# automation-v2.net
KiCad netlist of a schematic drawn in EAGLE
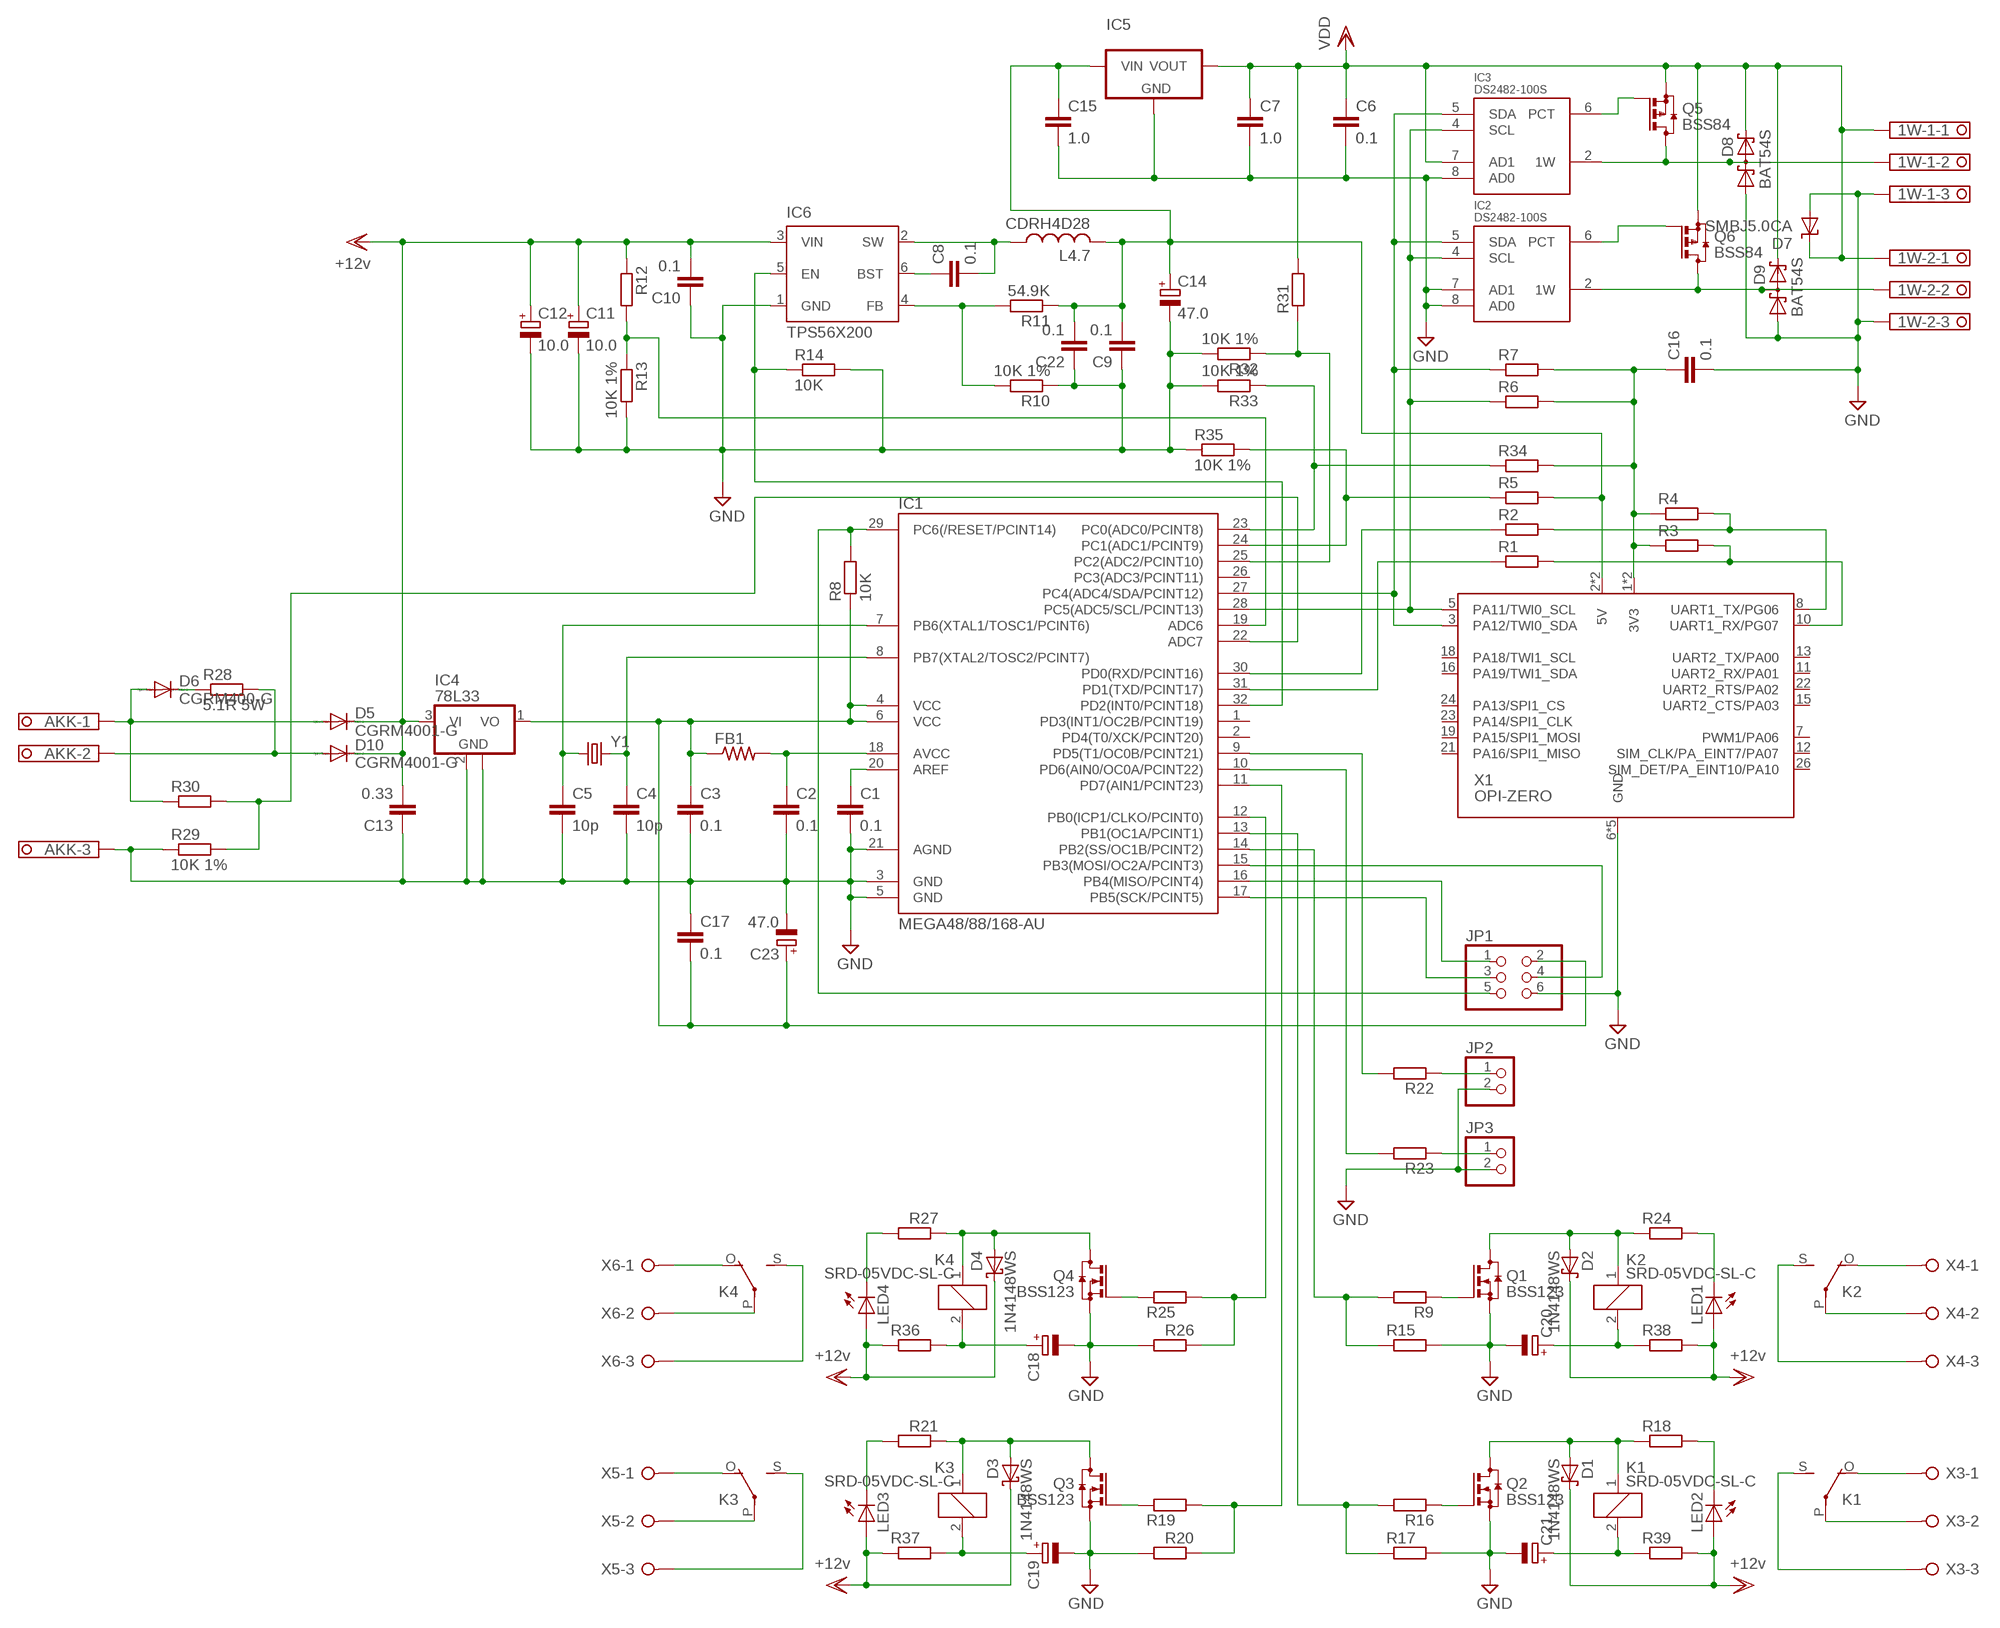
[diagram p0: schematic, sheet 1]

(export (version "E")
  (design (tool "Eeschema 10.0.6"))
  (components
    (comp (ref "1W-1")
      (value "1751251")
      (footprint "eagle-import:1751251")
      (libsource (lib "eagle-import") (part "1751251"))
    )
    (comp (ref "1W-2")
      (value "1751251")
      (footprint "eagle-import:1751251")
      (libsource (lib "eagle-import") (part "1751251"))
    )
    (comp (ref "AKK")
      (value "1751251")
      (footprint "eagle-import:1751251")
      (libsource (lib "eagle-import") (part "1751251"))
    )
    (comp (ref "C1")
      (value "0.1")
      (footprint "eagle-import:C0603")
      (libsource (lib "eagle-import") (part "C-EUC0603"))
    )
    (comp (ref "C2")
      (value "0.1")
      (footprint "eagle-import:C0603")
      (libsource (lib "eagle-import") (part "C-EUC0603"))
    )
    (comp (ref "C3")
      (value "0.1")
      (footprint "eagle-import:C0603")
      (libsource (lib "eagle-import") (part "C-EUC0603"))
    )
    (comp (ref "C4")
      (value "10p")
      (footprint "eagle-import:C0603")
      (libsource (lib "eagle-import") (part "C-EUC0603"))
    )
    (comp (ref "C5")
      (value "10p")
      (footprint "eagle-import:C0603")
      (libsource (lib "eagle-import") (part "C-EUC0603"))
    )
    (comp (ref "C6")
      (value "0.1")
      (footprint "eagle-import:C0603")
      (libsource (lib "eagle-import") (part "C-EUC0603"))
    )
    (comp (ref "C7")
      (value "1.0")
      (footprint "eagle-import:C0805")
      (libsource (lib "eagle-import") (part "C-EUC0805"))
    )
    (comp (ref "C8")
      (value "0.1")
      (footprint "eagle-import:C0805")
      (libsource (lib "eagle-import") (part "C-EUC0805"))
    )
    (comp (ref "C9")
      (value "0.1")
      (footprint "eagle-import:C0805")
      (libsource (lib "eagle-import") (part "C-EUC0805"))
    )
    (comp (ref "C10")
      (value "0.1")
      (footprint "eagle-import:C0805")
      (libsource (lib "eagle-import") (part "C-EUC0805"))
    )
    (comp (ref "C11")
      (value "10.0")
      (footprint "eagle-import:C_6032-28R")
      (libsource (lib "eagle-import") (part "CPOL-EUC/6032-28R"))
    )
    (comp (ref "C12")
      (value "10.0")
      (footprint "eagle-import:C_6032-28R")
      (libsource (lib "eagle-import") (part "CPOL-EUC/6032-28R"))
    )
    (comp (ref "C13")
      (value "0.33")
      (footprint "eagle-import:C0805")
      (libsource (lib "eagle-import") (part "C-EUC0805"))
    )
    (comp (ref "C14")
      (value "47.0")
      (footprint "eagle-import:B_3528-21R")
      (libsource (lib "eagle-import") (part "CPOL-EUB/3528-21R"))
    )
    (comp (ref "C15")
      (value "1.0")
      (footprint "eagle-import:C0805")
      (libsource (lib "eagle-import") (part "C-EUC0805"))
    )
    (comp (ref "C16")
      (value "0.1")
      (footprint "eagle-import:C0603")
      (libsource (lib "eagle-import") (part "C-EUC0603"))
    )
    (comp (ref "C17")
      (value "0.1")
      (footprint "eagle-import:C0603")
      (libsource (lib "eagle-import") (part "C-EUC0603"))
    )
    (comp (ref "C18")
      (value "CPOL-EUE5-10.5")
      (footprint "eagle-import:E5-10,5")
      (libsource (lib "eagle-import") (part "CPOL-EUE5-10.5"))
    )
    (comp (ref "C19")
      (value "CPOL-EUE5-10.5")
      (footprint "eagle-import:E5-10,5")
      (libsource (lib "eagle-import") (part "CPOL-EUE5-10.5"))
    )
    (comp (ref "C20")
      (value "CPOL-EUE5-10.5")
      (footprint "eagle-import:E5-10,5")
      (libsource (lib "eagle-import") (part "CPOL-EUE5-10.5"))
    )
    (comp (ref "C21")
      (value "CPOL-EUE5-10.5")
      (footprint "eagle-import:E5-10,5")
      (libsource (lib "eagle-import") (part "CPOL-EUE5-10.5"))
    )
    (comp (ref "C22")
      (value "0.1")
      (footprint "eagle-import:C0805")
      (libsource (lib "eagle-import") (part "C-EUC0805"))
    )
    (comp (ref "C23")
      (value "47.0")
      (footprint "eagle-import:B_3528-21R")
      (libsource (lib "eagle-import") (part "CPOL-EUB/3528-21R"))
    )
    (comp (ref "D1")
      (value "1N4148WS")
      (footprint "eagle-import:SOD323_ST")
      (libsource (lib "eagle-import") (part "BAT60J"))
    )
    (comp (ref "D2")
      (value "1N4148WS")
      (footprint "eagle-import:SOD323_ST")
      (libsource (lib "eagle-import") (part "BAT60J"))
    )
    (comp (ref "D3")
      (value "1N4148WS")
      (footprint "eagle-import:SOD323_ST")
      (libsource (lib "eagle-import") (part "BAT60J"))
    )
    (comp (ref "D4")
      (value "1N4148WS")
      (footprint "eagle-import:SOD323_ST")
      (libsource (lib "eagle-import") (part "BAT60J"))
    )
    (comp (ref "D5")
      (value "CGRM4001-G")
      (footprint "eagle-import:SOD-123_MINI-SMA")
      (libsource (lib "eagle-import") (part "CGRM400-G1"))
    )
    (comp (ref "D6")
      (value "CGRM400-G")
      (footprint "eagle-import:SOD-123_MINI-SMA")
      (libsource (lib "eagle-import") (part "CGRM400-G1"))
    )
    (comp (ref "D7")
      (value "SMBJ5.0CA")
      (footprint "eagle-import:SMBJ")
      (libsource (lib "eagle-import") (part "SUPPRESSOR-SMBJ"))
    )
    (comp (ref "D8")
      (value "BAT54S")
      (footprint "eagle-import:SOT23")
      (libsource (lib "eagle-import") (part "BAT54S"))
    )
    (comp (ref "D9")
      (value "BAT54S")
      (footprint "eagle-import:SOT23")
      (libsource (lib "eagle-import") (part "BAT54S"))
    )
    (comp (ref "D10")
      (value "CGRM4001-G")
      (footprint "eagle-import:SOD-123_MINI-SMA")
      (libsource (lib "eagle-import") (part "CGRM400-G1"))
    )
    (comp (ref "FB1")
      (value "R-US_R0805")
      (footprint "eagle-import:R0805")
      (libsource (lib "eagle-import") (part "R-US_R0805"))
    )
    (comp (ref "IC1")
      (value "MEGA48/88/168-AU")
      (footprint "eagle-import:TQFP32-08")
      (libsource (lib "eagle-import") (part "MEGA48/88/168-AU"))
    )
    (comp (ref "IC2")
      (value "DS2482-100S")
      (footprint "eagle-import:SO08")
      (libsource (lib "eagle-import") (part "DS2482-100S"))
    )
    (comp (ref "IC3")
      (value "DS2482-100S")
      (footprint "eagle-import:SO08")
      (libsource (lib "eagle-import") (part "DS2482-100S"))
    )
    (comp (ref "IC4")
      (value "78L33")
      (footprint "eagle-import:SOT89")
      (libsource (lib "eagle-import") (part "78LF05"))
    )
    (comp (ref "IC5")
      (value "MCP1702SOT23")
      (footprint "eagle-import:SOT23-3-ROTATED")
      (libsource (lib "eagle-import") (part "MCP1702SOT23"))
    )
    (comp (ref "IC6")
      (value "TPS56X200")
      (footprint "eagle-import:TSOT23-6_DDC")
      (libsource (lib "eagle-import") (part "TPS56X200"))
    )
    (comp (ref "JP1")
      (value "PINHD-2X3")
      (footprint "eagle-import:2X03")
      (libsource (lib "eagle-import") (part "PINHD-2X3"))
    )
    (comp (ref "JP2")
      (value "PINHD-1X2")
      (footprint "eagle-import:1X02")
      (libsource (lib "eagle-import") (part "PINHD-1X2"))
    )
    (comp (ref "JP3")
      (value "PINHD-1X2")
      (footprint "eagle-import:1X02")
      (libsource (lib "eagle-import") (part "PINHD-1X2"))
    )
    (comp (ref "K1")
      (value "SRD-05VDC-SL-C")
      (footprint "eagle-import:NRP18")
      (libsource (lib "eagle-import") (part "ZF112S"))
    )
    (comp (ref "K2")
      (value "SRD-05VDC-SL-C")
      (footprint "eagle-import:NRP18")
      (libsource (lib "eagle-import") (part "ZF112S"))
    )
    (comp (ref "K3")
      (value "SRD-05VDC-SL-C")
      (footprint "eagle-import:NRP18")
      (libsource (lib "eagle-import") (part "ZF112S"))
    )
    (comp (ref "K4")
      (value "SRD-05VDC-SL-C")
      (footprint "eagle-import:NRP18")
      (libsource (lib "eagle-import") (part "ZF112S"))
    )
    (comp (ref "L4.7")
      (value "CDRH4D28")
      (footprint "eagle-import:CDRH4D28")
      (libsource (lib "eagle-import") (part "CDRH4D28"))
    )
    (comp (ref "LED1")
      (value "LEDSML0805")
      (footprint "eagle-import:SML0805")
      (libsource (lib "eagle-import") (part "LEDSML0805"))
    )
    (comp (ref "LED2")
      (value "LEDSML0805")
      (footprint "eagle-import:SML0805")
      (libsource (lib "eagle-import") (part "LEDSML0805"))
    )
    (comp (ref "LED3")
      (value "LEDSML0805")
      (footprint "eagle-import:SML0805")
      (libsource (lib "eagle-import") (part "LEDSML0805"))
    )
    (comp (ref "LED4")
      (value "LEDSML0805")
      (footprint "eagle-import:SML0805")
      (libsource (lib "eagle-import") (part "LEDSML0805"))
    )
    (comp (ref "Q1")
      (value "BSS123")
      (footprint "eagle-import:SOT23")
      (libsource (lib "eagle-import") (part "BSS123"))
    )
    (comp (ref "Q2")
      (value "BSS123")
      (footprint "eagle-import:SOT23")
      (libsource (lib "eagle-import") (part "BSS123"))
    )
    (comp (ref "Q3")
      (value "BSS123")
      (footprint "eagle-import:SOT23")
      (libsource (lib "eagle-import") (part "BSS123"))
    )
    (comp (ref "Q4")
      (value "BSS123")
      (footprint "eagle-import:SOT23")
      (libsource (lib "eagle-import") (part "BSS123"))
    )
    (comp (ref "Q5")
      (value "BSS84")
      (footprint "eagle-import:SOT23")
      (libsource (lib "eagle-import") (part "BSS84"))
    )
    (comp (ref "Q6")
      (value "BSS84")
      (footprint "eagle-import:SOT23")
      (libsource (lib "eagle-import") (part "BSS84"))
    )
    (comp (ref "R1")
      (value "R-EU_R0603")
      (footprint "eagle-import:R0603")
      (libsource (lib "eagle-import") (part "R-EU_R0603"))
    )
    (comp (ref "R2")
      (value "R-EU_R0603")
      (footprint "eagle-import:R0603")
      (libsource (lib "eagle-import") (part "R-EU_R0603"))
    )
    (comp (ref "R3")
      (value "R-EU_R0603")
      (footprint "eagle-import:R0603")
      (libsource (lib "eagle-import") (part "R-EU_R0603"))
    )
    (comp (ref "R4")
      (value "R-EU_R0603")
      (footprint "eagle-import:R0603")
      (libsource (lib "eagle-import") (part "R-EU_R0603"))
    )
    (comp (ref "R5")
      (value "R-EU_R0603")
      (footprint "eagle-import:R0603")
      (libsource (lib "eagle-import") (part "R-EU_R0603"))
    )
    (comp (ref "R6")
      (value "R-EU_R0603")
      (footprint "eagle-import:R0603")
      (libsource (lib "eagle-import") (part "R-EU_R0603"))
    )
    (comp (ref "R7")
      (value "R-EU_R0603")
      (footprint "eagle-import:R0603")
      (libsource (lib "eagle-import") (part "R-EU_R0603"))
    )
    (comp (ref "R8")
      (value "10K")
      (footprint "eagle-import:R0603")
      (libsource (lib "eagle-import") (part "R-EU_R0603"))
    )
    (comp (ref "R9")
      (value "R-EU_R0603")
      (footprint "eagle-import:R0603")
      (libsource (lib "eagle-import") (part "R-EU_R0603"))
    )
    (comp (ref "R10")
      (value "10K 1%")
      (footprint "eagle-import:R0603")
      (libsource (lib "eagle-import") (part "R-EU_R0603"))
    )
    (comp (ref "R11")
      (value "54.9K")
      (footprint "eagle-import:R0603")
      (libsource (lib "eagle-import") (part "R-EU_R0603"))
    )
    (comp (ref "R12")
      (value "R-EU_R0603")
      (footprint "eagle-import:R0603")
      (libsource (lib "eagle-import") (part "R-EU_R0603"))
    )
    (comp (ref "R13")
      (value "10K 1%")
      (footprint "eagle-import:R0603")
      (libsource (lib "eagle-import") (part "R-EU_R0603"))
    )
    (comp (ref "R14")
      (value "10K")
      (footprint "eagle-import:R0603")
      (libsource (lib "eagle-import") (part "R-EU_R0603"))
    )
    (comp (ref "R15")
      (value "R-EU_R0603")
      (footprint "eagle-import:R0603")
      (libsource (lib "eagle-import") (part "R-EU_R0603"))
    )
    (comp (ref "R16")
      (value "R-EU_R0603")
      (footprint "eagle-import:R0603")
      (libsource (lib "eagle-import") (part "R-EU_R0603"))
    )
    (comp (ref "R17")
      (value "R-EU_R0603")
      (footprint "eagle-import:R0603")
      (libsource (lib "eagle-import") (part "R-EU_R0603"))
    )
    (comp (ref "R18")
      (value "R-EU_R0603")
      (footprint "eagle-import:R0603")
      (libsource (lib "eagle-import") (part "R-EU_R0603"))
    )
    (comp (ref "R19")
      (value "R-EU_R0603")
      (footprint "eagle-import:R0603")
      (libsource (lib "eagle-import") (part "R-EU_R0603"))
    )
    (comp (ref "R20")
      (value "R-EU_R0603")
      (footprint "eagle-import:R0603")
      (libsource (lib "eagle-import") (part "R-EU_R0603"))
    )
    (comp (ref "R21")
      (value "R-EU_R0603")
      (footprint "eagle-import:R0603")
      (libsource (lib "eagle-import") (part "R-EU_R0603"))
    )
    (comp (ref "R22")
      (value "R-EU_R0603")
      (footprint "eagle-import:R0603")
      (libsource (lib "eagle-import") (part "R-EU_R0603"))
    )
    (comp (ref "R23")
      (value "R-EU_R0603")
      (footprint "eagle-import:R0603")
      (libsource (lib "eagle-import") (part "R-EU_R0603"))
    )
    (comp (ref "R24")
      (value "R-EU_R0603")
      (footprint "eagle-import:R0603")
      (libsource (lib "eagle-import") (part "R-EU_R0603"))
    )
    (comp (ref "R25")
      (value "R-EU_R0603")
      (footprint "eagle-import:R0603")
      (libsource (lib "eagle-import") (part "R-EU_R0603"))
    )
    (comp (ref "R26")
      (value "R-EU_R0603")
      (footprint "eagle-import:R0603")
      (libsource (lib "eagle-import") (part "R-EU_R0603"))
    )
    (comp (ref "R27")
      (value "R-EU_R0603")
      (footprint "eagle-import:R0603")
      (libsource (lib "eagle-import") (part "R-EU_R0603"))
    )
    (comp (ref "R28")
      (value "5.1R 5W")
      (footprint "eagle-import:VTA55")
      (libsource (lib "eagle-import") (part "R-EU_VTA55"))
    )
    (comp (ref "R29")
      (value "10K 1%")
      (footprint "eagle-import:R0603")
      (libsource (lib "eagle-import") (part "R-EU_R0603"))
    )
    (comp (ref "R30")
      (value "R-EU_R0603")
      (footprint "eagle-import:R0603")
      (libsource (lib "eagle-import") (part "R-EU_R0603"))
    )
    (comp (ref "R31")
      (value "R-EU_R0603")
      (footprint "eagle-import:R0603")
      (libsource (lib "eagle-import") (part "R-EU_R0603"))
    )
    (comp (ref "R32")
      (value "10K 1%")
      (footprint "eagle-import:R0603")
      (libsource (lib "eagle-import") (part "R-EU_R0603"))
    )
    (comp (ref "R33")
      (value "10K 1%")
      (footprint "eagle-import:R0603")
      (libsource (lib "eagle-import") (part "R-EU_R0603"))
    )
    (comp (ref "R34")
      (value "R-EU_R0603")
      (footprint "eagle-import:R0603")
      (libsource (lib "eagle-import") (part "R-EU_R0603"))
    )
    (comp (ref "R35")
      (value "10K 1%")
      (footprint "eagle-import:R0603")
      (libsource (lib "eagle-import") (part "R-EU_R0603"))
    )
    (comp (ref "R36")
      (value "R-EU_M1206")
      (footprint "eagle-import:M1206")
      (libsource (lib "eagle-import") (part "R-EU_M1206"))
    )
    (comp (ref "R37")
      (value "R-EU_M1206")
      (footprint "eagle-import:M1206")
      (libsource (lib "eagle-import") (part "R-EU_M1206"))
    )
    (comp (ref "R38")
      (value "R-EU_M1206")
      (footprint "eagle-import:M1206")
      (libsource (lib "eagle-import") (part "R-EU_M1206"))
    )
    (comp (ref "R39")
      (value "R-EU_M1206")
      (footprint "eagle-import:M1206")
      (libsource (lib "eagle-import") (part "R-EU_M1206"))
    )
    (comp (ref "X1")
      (value "OPI-ZERO")
      (footprint "eagle-import:OPI0")
      (libsource (lib "eagle-import") (part "OPI-ZERO"))
    )
    (comp (ref "X3")
      (value "W237-03P")
      (footprint "eagle-import:W237-133")
      (libsource (lib "eagle-import") (part "W237-03P"))
    )
    (comp (ref "X4")
      (value "W237-03P")
      (footprint "eagle-import:W237-133")
      (libsource (lib "eagle-import") (part "W237-03P"))
    )
    (comp (ref "X5")
      (value "W237-03P")
      (footprint "eagle-import:W237-133")
      (libsource (lib "eagle-import") (part "W237-03P"))
    )
    (comp (ref "X6")
      (value "W237-03P")
      (footprint "eagle-import:W237-133")
      (libsource (lib "eagle-import") (part "W237-03P"))
    )
    (comp (ref "Y1")
      (value "CRYSTALHC49US")
      (footprint "eagle-import:HC49US")
      (libsource (lib "eagle-import") (part "CRYSTALHC49US"))
    )
  )
  (nets
    (net (code "1") (name "+12v") (class "Default")
      (node (ref "C10") (pin "2") (pinfunction "2_2") (pintype "passive"))
      (node (ref "C11") (pin "+") (pinfunction "+_+") (pintype "passive"))
      (node (ref "C12") (pin "+") (pinfunction "+_+") (pintype "passive"))
      (node (ref "C13") (pin "2") (pinfunction "2_2") (pintype "passive"))
      (node (ref "D1") (pin "C") (pinfunction "C_C") (pintype "passive"))
      (node (ref "D10") (pin "C") (pinfunction "C_C") (pintype "passive"))
      (node (ref "D2") (pin "C") (pinfunction "C_C") (pintype "passive"))
      (node (ref "D3") (pin "C") (pinfunction "C_C") (pintype "passive"))
      (node (ref "D4") (pin "C") (pinfunction "C_C") (pintype "passive"))
      (node (ref "D5") (pin "C") (pinfunction "C_C") (pintype "passive"))
      (node (ref "IC4") (pin "3") (pinfunction "VI_3") (pintype "input"))
      (node (ref "IC6") (pin "3") (pinfunction "VIN_3") (pintype "input"))
      (node (ref "LED1") (pin "A") (pinfunction "A_A") (pintype "passive"))
      (node (ref "LED2") (pin "A") (pinfunction "A_A") (pintype "passive"))
      (node (ref "LED3") (pin "A") (pinfunction "A_A") (pintype "passive"))
      (node (ref "LED4") (pin "A") (pinfunction "A_A") (pintype "passive"))
      (node (ref "R12") (pin "1") (pinfunction "1_1") (pintype "passive"))
      (node (ref "R36") (pin "1") (pinfunction "1_1") (pintype "passive"))
      (node (ref "R37") (pin "1") (pinfunction "1_1") (pintype "passive"))
      (node (ref "R38") (pin "2") (pinfunction "2_2") (pintype "passive"))
      (node (ref "R39") (pin "2") (pinfunction "2_2") (pintype "passive"))
    )
    (net (code "2") (name "GND") (class "Default")
      (node (ref "1W-1") (pin "3") (pinfunction "K_3") (pintype "passive"))
      (node (ref "1W-2") (pin "3") (pinfunction "K_3") (pintype "passive"))
      (node (ref "AKK") (pin "3") (pinfunction "K_3") (pintype "passive"))
      (node (ref "C1") (pin "2") (pinfunction "2_2") (pintype "passive"))
      (node (ref "C10") (pin "1") (pinfunction "1_1") (pintype "passive"))
      (node (ref "C11") (pin "-") (pinfunction "-_-") (pintype "passive"))
      (node (ref "C12") (pin "-") (pinfunction "-_-") (pintype "passive"))
      (node (ref "C13") (pin "1") (pinfunction "1_1") (pintype "passive"))
      (node (ref "C14") (pin "-") (pinfunction "-_-") (pintype "passive"))
      (node (ref "C15") (pin "2") (pinfunction "2_2") (pintype "passive"))
      (node (ref "C16") (pin "2") (pinfunction "2_2") (pintype "passive"))
      (node (ref "C17") (pin "1") (pinfunction "1_1") (pintype "passive"))
      (node (ref "C18") (pin "-") (pinfunction "-_-") (pintype "passive"))
      (node (ref "C19") (pin "-") (pinfunction "-_-") (pintype "passive"))
      (node (ref "C2") (pin "2") (pinfunction "2_2") (pintype "passive"))
      (node (ref "C20") (pin "-") (pinfunction "-_-") (pintype "passive"))
      (node (ref "C21") (pin "-") (pinfunction "-_-") (pintype "passive"))
      (node (ref "C22") (pin "1") (pinfunction "1_1") (pintype "passive"))
      (node (ref "C23") (pin "-") (pinfunction "-_-") (pintype "passive"))
      (node (ref "C3") (pin "2") (pinfunction "2_2") (pintype "passive"))
      (node (ref "C4") (pin "2") (pinfunction "2_2") (pintype "passive"))
      (node (ref "C5") (pin "2") (pinfunction "2_2") (pintype "passive"))
      (node (ref "C6") (pin "2") (pinfunction "2_2") (pintype "passive"))
      (node (ref "C7") (pin "2") (pinfunction "2_2") (pintype "passive"))
      (node (ref "C9") (pin "1") (pinfunction "1_1") (pintype "passive"))
      (node (ref "D7") (pin "A") (pinfunction "A_A") (pintype "passive"))
      (node (ref "D8") (pin "1") (pinfunction "A1_1") (pintype "passive"))
      (node (ref "D9") (pin "1") (pinfunction "A1_1") (pintype "passive"))
      (node (ref "IC1") (pin "21") (pinfunction "AGND_21") (pintype "power_in"))
      (node (ref "IC1") (pin "3") (pinfunction "GND_3") (pintype "power_in"))
      (node (ref "IC1") (pin "5") (pinfunction "GND_5") (pintype "power_in"))
      (node (ref "IC2") (pin "7") (pinfunction "AD1_7") (pintype "input"))
      (node (ref "IC2") (pin "8") (pinfunction "AD0_8") (pintype "input"))
      (node (ref "IC3") (pin "8") (pinfunction "AD0_8") (pintype "input"))
      (node (ref "IC4") (pin "2") (pinfunction "GND_2") (pintype "passive"))
      (node (ref "IC4") (pin "2@1") (pinfunction "GND_2@1") (pintype "passive"))
      (node (ref "IC5") (pin "1") (pinfunction "GND_1") (pintype "passive"))
      (node (ref "IC6") (pin "1") (pinfunction "GND_1") (pintype "power_in"))
      (node (ref "JP1") (pin "6") (pinfunction "6_6") (pintype "passive"))
      (node (ref "JP2") (pin "2") (pinfunction "2_2") (pintype "passive"))
      (node (ref "JP3") (pin "2") (pinfunction "2_2") (pintype "passive"))
      (node (ref "Q1") (pin "2") (pinfunction "S_2") (pintype "passive"))
      (node (ref "Q2") (pin "2") (pinfunction "S_2") (pintype "passive"))
      (node (ref "Q3") (pin "2") (pinfunction "S_2") (pintype "passive"))
      (node (ref "Q4") (pin "2") (pinfunction "S_2") (pintype "passive"))
      (node (ref "R10") (pin "1") (pinfunction "1_1") (pintype "passive"))
      (node (ref "R13") (pin "2") (pinfunction "2_2") (pintype "passive"))
      (node (ref "R14") (pin "2") (pinfunction "2_2") (pintype "passive"))
      (node (ref "R15") (pin "2") (pinfunction "2_2") (pintype "passive"))
      (node (ref "R17") (pin "2") (pinfunction "2_2") (pintype "passive"))
      (node (ref "R20") (pin "2") (pinfunction "2_2") (pintype "passive"))
      (node (ref "R26") (pin "2") (pinfunction "2_2") (pintype "passive"))
      (node (ref "R29") (pin "1") (pinfunction "1_1") (pintype "passive"))
      (node (ref "R32") (pin "2") (pinfunction "2_2") (pintype "passive"))
      (node (ref "R33") (pin "2") (pinfunction "2_2") (pintype "passive"))
      (node (ref "R35") (pin "1") (pinfunction "1_1") (pintype "passive"))
      (node (ref "X1") (pin "14") (pinfunction "GND_14") (pintype "power_in"))
      (node (ref "X1") (pin "20") (pinfunction "GND_20") (pintype "power_in"))
      (node (ref "X1") (pin "25") (pinfunction "GND_25") (pintype "power_in"))
      (node (ref "X1") (pin "6") (pinfunction "GND_6") (pintype "power_in"))
      (node (ref "X1") (pin "9") (pinfunction "GND_9") (pintype "power_in"))
    )
    (net (code "3") (name "Net-(1W-1B-K)") (class "Default")
      (node (ref "1W-1") (pin "2") (pinfunction "K_2") (pintype "passive"))
      (node (ref "D8") (pin "3") (pinfunction "C1A2_3") (pintype "passive"))
      (node (ref "IC3") (pin "2") (pinfunction "1W_2") (pintype "open_collector"))
      (node (ref "Q5") (pin "3") (pinfunction "D_3") (pintype "passive"))
    )
    (net (code "4") (name "Net-(1W-2B-K)") (class "Default")
      (node (ref "1W-2") (pin "2") (pinfunction "K_2") (pintype "passive"))
      (node (ref "D9") (pin "3") (pinfunction "C1A2_3") (pintype "passive"))
      (node (ref "IC2") (pin "2") (pinfunction "1W_2") (pintype "open_collector"))
      (node (ref "Q6") (pin "3") (pinfunction "D_3") (pintype "passive"))
    )
    (net (code "5") (name "Net-(AKKA-K)") (class "Default")
      (node (ref "AKK") (pin "1") (pinfunction "K_1") (pintype "passive"))
      (node (ref "D5") (pin "A") (pinfunction "A_A") (pintype "passive"))
      (node (ref "D6") (pin "A") (pinfunction "A_A") (pintype "passive"))
      (node (ref "R30") (pin "1") (pinfunction "1_1") (pintype "passive"))
    )
    (net (code "6") (name "Net-(AKKB-K)") (class "Default")
      (node (ref "AKK") (pin "2") (pinfunction "K_2") (pintype "passive"))
      (node (ref "D10") (pin "A") (pinfunction "A_A") (pintype "passive"))
      (node (ref "R28") (pin "2") (pinfunction "2_2") (pintype "passive"))
    )
    (net (code "7") (name "Net-(C16-Pad1)") (class "Default")
      (node (ref "C16") (pin "1") (pinfunction "1_1") (pintype "passive"))
      (node (ref "R3") (pin "1") (pinfunction "1_1") (pintype "passive"))
      (node (ref "R34") (pin "2") (pinfunction "2_2") (pintype "passive"))
      (node (ref "R4") (pin "1") (pinfunction "1_1") (pintype "passive"))
      (node (ref "R6") (pin "2") (pinfunction "2_2") (pintype "passive"))
      (node (ref "R7") (pin "2") (pinfunction "2_2") (pintype "passive"))
      (node (ref "X1") (pin "1") (pinfunction "3V3_1") (pintype "power_in"))
      (node (ref "X1") (pin "17") (pinfunction "3V3_17") (pintype "power_in"))
    )
    (net (code "8") (name "Net-(C18-Pad+)") (class "Default")
      (node (ref "C18") (pin "+") (pinfunction "+_+") (pintype "passive"))
      (node (ref "K4") (pin "2") (pinfunction "2_2") (pintype "passive"))
      (node (ref "R36") (pin "2") (pinfunction "2_2") (pintype "passive"))
    )
    (net (code "9") (name "Net-(C19-Pad+)") (class "Default")
      (node (ref "C19") (pin "+") (pinfunction "+_+") (pintype "passive"))
      (node (ref "K3") (pin "2") (pinfunction "2_2") (pintype "passive"))
      (node (ref "R37") (pin "2") (pinfunction "2_2") (pintype "passive"))
    )
    (net (code "10") (name "Net-(C20-Pad+)") (class "Default")
      (node (ref "C20") (pin "+") (pinfunction "+_+") (pintype "passive"))
      (node (ref "K2") (pin "2") (pinfunction "2_2") (pintype "passive"))
      (node (ref "R38") (pin "1") (pinfunction "1_1") (pintype "passive"))
    )
    (net (code "11") (name "Net-(C21-Pad+)") (class "Default")
      (node (ref "C21") (pin "+") (pinfunction "+_+") (pintype "passive"))
      (node (ref "K1") (pin "2") (pinfunction "2_2") (pintype "passive"))
      (node (ref "R39") (pin "1") (pinfunction "1_1") (pintype "passive"))
    )
    (net (code "12") (name "Net-(D6-PadC)") (class "Default")
      (node (ref "D6") (pin "C") (pinfunction "C_C") (pintype "passive"))
      (node (ref "R28") (pin "1") (pinfunction "1_1") (pintype "passive"))
    )
    (net (code "13") (name "Net-(IC1-ADC6)") (class "Default")
      (node (ref "IC1") (pin "19") (pinfunction "ADC6_19") (pintype "passive"))
      (node (ref "R12") (pin "2") (pinfunction "2_2") (pintype "passive"))
      (node (ref "R13") (pin "1") (pinfunction "1_1") (pintype "passive"))
    )
    (net (code "14") (name "Net-(IC1-ADC7)") (class "Default")
      (node (ref "IC1") (pin "22") (pinfunction "ADC7_22") (pintype "passive"))
      (node (ref "R29") (pin "2") (pinfunction "2_2") (pintype "passive"))
      (node (ref "R30") (pin "2") (pinfunction "2_2") (pintype "passive"))
    )
    (net (code "15") (name "Net-(IC1-AREF)") (class "Default")
      (node (ref "C1") (pin "1") (pinfunction "1_1") (pintype "passive"))
      (node (ref "IC1") (pin "20") (pinfunction "AREF_20") (pintype "passive"))
    )
    (net (code "16") (name "Net-(IC1-AVCC)") (class "Default")
      (node (ref "C2") (pin "1") (pinfunction "1_1") (pintype "passive"))
      (node (ref "FB1") (pin "2") (pinfunction "2_2") (pintype "passive"))
      (node (ref "IC1") (pin "18") (pinfunction "AVCC_18") (pintype "passive"))
    )
    (net (code "17") (name "Net-(IC1-PB0(ICP1{slash}CLKO{slash}PCINT0))") (class "Default")
      (node (ref "IC1") (pin "12") (pinfunction "PB0(ICP1/CLKO/PCINT0)_12") (pintype "bidirectional"))
      (node (ref "R25") (pin "2") (pinfunction "2_2") (pintype "passive"))
      (node (ref "R26") (pin "1") (pinfunction "1_1") (pintype "passive"))
    )
    (net (code "18") (name "Net-(IC1-PB1(OC1A{slash}PCINT1))") (class "Default")
      (node (ref "IC1") (pin "13") (pinfunction "PB1(OC1A/PCINT1)_13") (pintype "bidirectional"))
      (node (ref "R16") (pin "2") (pinfunction "2_2") (pintype "passive"))
      (node (ref "R17") (pin "1") (pinfunction "1_1") (pintype "passive"))
    )
    (net (code "19") (name "Net-(IC1-PB2(SS{slash}OC1B{slash}PCINT2))") (class "Default")
      (node (ref "IC1") (pin "14") (pinfunction "PB2(SS/OC1B/PCINT2)_14") (pintype "bidirectional"))
      (node (ref "R15") (pin "1") (pinfunction "1_1") (pintype "passive"))
      (node (ref "R9") (pin "2") (pinfunction "2_2") (pintype "passive"))
    )
    (net (code "20") (name "Net-(IC1-PB3(MOSI{slash}OC2A{slash}PCINT3))") (class "Default")
      (node (ref "IC1") (pin "15") (pinfunction "PB3(MOSI/OC2A/PCINT3)_15") (pintype "bidirectional"))
      (node (ref "JP1") (pin "4") (pinfunction "4_4") (pintype "passive"))
    )
    (net (code "21") (name "Net-(IC1-PB4(MISO{slash}PCINT4))") (class "Default")
      (node (ref "IC1") (pin "16") (pinfunction "PB4(MISO/PCINT4)_16") (pintype "bidirectional"))
      (node (ref "JP1") (pin "1") (pinfunction "1_1") (pintype "passive"))
    )
    (net (code "22") (name "Net-(IC1-PB5(SCK{slash}PCINT5))") (class "Default")
      (node (ref "IC1") (pin "17") (pinfunction "PB5(SCK/PCINT5)_17") (pintype "bidirectional"))
      (node (ref "JP1") (pin "3") (pinfunction "3_3") (pintype "passive"))
    )
    (net (code "23") (name "Net-(IC1-PB6(XTAL1{slash}TOSC1{slash}PCINT6))") (class "Default")
      (node (ref "C5") (pin "1") (pinfunction "1_1") (pintype "passive"))
      (node (ref "IC1") (pin "7") (pinfunction "PB6(XTAL1/TOSC1/PCINT6)_7") (pintype "bidirectional"))
      (node (ref "Y1") (pin "1") (pinfunction "1_1") (pintype "passive"))
    )
    (net (code "24") (name "Net-(IC1-PB7(XTAL2{slash}TOSC2{slash}PCINT7))") (class "Default")
      (node (ref "C4") (pin "1") (pinfunction "1_1") (pintype "passive"))
      (node (ref "IC1") (pin "8") (pinfunction "PB7(XTAL2/TOSC2/PCINT7)_8") (pintype "bidirectional"))
      (node (ref "Y1") (pin "2") (pinfunction "2_2") (pintype "passive"))
    )
    (net (code "25") (name "Net-(IC1-PC0(ADC0{slash}PCINT8))") (class "Default")
      (node (ref "IC1") (pin "23") (pinfunction "PC0(ADC0/PCINT8)_23") (pintype "bidirectional"))
      (node (ref "R33") (pin "1") (pinfunction "1_1") (pintype "passive"))
      (node (ref "R34") (pin "1") (pinfunction "1_1") (pintype "passive"))
    )
    (net (code "26") (name "Net-(IC1-PC1(ADC1{slash}PCINT9))") (class "Default")
      (node (ref "IC1") (pin "24") (pinfunction "PC1(ADC1/PCINT9)_24") (pintype "bidirectional"))
      (node (ref "R35") (pin "2") (pinfunction "2_2") (pintype "passive"))
      (node (ref "R5") (pin "1") (pinfunction "1_1") (pintype "passive"))
    )
    (net (code "27") (name "Net-(IC1-PC2(ADC2{slash}PCINT10))") (class "Default")
      (node (ref "IC1") (pin "25") (pinfunction "PC2(ADC2/PCINT10)_25") (pintype "bidirectional"))
      (node (ref "R31") (pin "1") (pinfunction "1_1") (pintype "passive"))
      (node (ref "R32") (pin "1") (pinfunction "1_1") (pintype "passive"))
    )
    (net (code "28") (name "Net-(IC1-PC4(ADC4{slash}SDA{slash}PCINT12))") (class "Default")
      (node (ref "IC1") (pin "27") (pinfunction "PC4(ADC4/SDA/PCINT12)_27") (pintype "bidirectional"))
      (node (ref "IC2") (pin "5") (pinfunction "SDA_5") (pintype "bidirectional"))
      (node (ref "IC3") (pin "5") (pinfunction "SDA_5") (pintype "bidirectional"))
      (node (ref "R7") (pin "1") (pinfunction "1_1") (pintype "passive"))
      (node (ref "X1") (pin "3") (pinfunction "PA12/TWI0_SDA_3") (pintype "bidirectional"))
    )
    (net (code "29") (name "Net-(IC1-PC5(ADC5{slash}SCL{slash}PCINT13))") (class "Default")
      (node (ref "IC1") (pin "28") (pinfunction "PC5(ADC5/SCL/PCINT13)_28") (pintype "bidirectional"))
      (node (ref "IC2") (pin "4") (pinfunction "SCL_4") (pintype "input"))
      (node (ref "IC3") (pin "4") (pinfunction "SCL_4") (pintype "input"))
      (node (ref "R6") (pin "1") (pinfunction "1_1") (pintype "passive"))
      (node (ref "X1") (pin "5") (pinfunction "PA11/TWI0_SCL_5") (pintype "bidirectional"))
    )
    (net (code "30") (name "Net-(IC1-PC6({slash}RESET{slash}PCINT14))") (class "Default")
      (node (ref "IC1") (pin "29") (pinfunction "PC6(/RESET/PCINT14)_29") (pintype "bidirectional"))
      (node (ref "JP1") (pin "5") (pinfunction "5_5") (pintype "passive"))
      (node (ref "R8") (pin "2") (pinfunction "2_2") (pintype "passive"))
    )
    (net (code "31") (name "Net-(IC1-PD0(RXD{slash}PCINT16))") (class "Default")
      (node (ref "IC1") (pin "30") (pinfunction "PD0(RXD/PCINT16)_30") (pintype "bidirectional"))
      (node (ref "R2") (pin "1") (pinfunction "1_1") (pintype "passive"))
    )
    (net (code "32") (name "Net-(IC1-PD1(TXD{slash}PCINT17))") (class "Default")
      (node (ref "IC1") (pin "31") (pinfunction "PD1(TXD/PCINT17)_31") (pintype "bidirectional"))
      (node (ref "R1") (pin "1") (pinfunction "1_1") (pintype "passive"))
    )
    (net (code "33") (name "Net-(IC1-PD2(INT0{slash}PCINT18))") (class "Default")
      (node (ref "IC1") (pin "32") (pinfunction "PD2(INT0/PCINT18)_32") (pintype "bidirectional"))
      (node (ref "IC6") (pin "5") (pinfunction "EN_5") (pintype "input"))
      (node (ref "R14") (pin "1") (pinfunction "1_1") (pintype "passive"))
    )
    (net (code "34") (name "Net-(IC1-PD5(T1{slash}OC0B{slash}PCINT21))") (class "Default")
      (node (ref "IC1") (pin "9") (pinfunction "PD5(T1/OC0B/PCINT21)_9") (pintype "bidirectional"))
      (node (ref "R22") (pin "2") (pinfunction "2_2") (pintype "passive"))
    )
    (net (code "35") (name "Net-(IC1-PD6(AIN0{slash}OC0A{slash}PCINT22))") (class "Default")
      (node (ref "IC1") (pin "10") (pinfunction "PD6(AIN0/OC0A/PCINT22)_10") (pintype "bidirectional"))
      (node (ref "R23") (pin "2") (pinfunction "2_2") (pintype "passive"))
    )
    (net (code "36") (name "Net-(IC1-PD7(AIN1{slash}PCINT23))") (class "Default")
      (node (ref "IC1") (pin "11") (pinfunction "PD7(AIN1/PCINT23)_11") (pintype "bidirectional"))
      (node (ref "R19") (pin "2") (pinfunction "2_2") (pintype "passive"))
      (node (ref "R20") (pin "1") (pinfunction "1_1") (pintype "passive"))
    )
    (net (code "37") (name "Net-(IC2A-PCT)") (class "Default")
      (node (ref "IC2") (pin "6") (pinfunction "PCT_6") (pintype "output"))
      (node (ref "Q6") (pin "1") (pinfunction "G_1") (pintype "passive"))
    )
    (net (code "38") (name "Net-(IC3A-PCT)") (class "Default")
      (node (ref "IC3") (pin "6") (pinfunction "PCT_6") (pintype "output"))
      (node (ref "Q5") (pin "1") (pinfunction "G_1") (pintype "passive"))
    )
    (net (code "39") (name "Net-(IC4-VO)") (class "Default")
      (node (ref "C17") (pin "2") (pinfunction "2_2") (pintype "passive"))
      (node (ref "C23") (pin "+") (pinfunction "+_+") (pintype "passive"))
      (node (ref "C3") (pin "1") (pinfunction "1_1") (pintype "passive"))
      (node (ref "FB1") (pin "1") (pinfunction "1_1") (pintype "passive"))
      (node (ref "IC1") (pin "4") (pinfunction "VCC_4") (pintype "power_in"))
      (node (ref "IC1") (pin "6") (pinfunction "VCC_6") (pintype "power_in"))
      (node (ref "IC4") (pin "1") (pinfunction "VO_1") (pintype "passive"))
      (node (ref "JP1") (pin "2") (pinfunction "2_2") (pintype "passive"))
      (node (ref "R8") (pin "1") (pinfunction "1_1") (pintype "passive"))
    )
    (net (code "40") (name "Net-(IC5-VIN)") (class "Default")
      (node (ref "C14") (pin "+") (pinfunction "+_+") (pintype "passive"))
      (node (ref "C15") (pin "1") (pinfunction "1_1") (pintype "passive"))
      (node (ref "C22") (pin "2") (pinfunction "2_2") (pintype "passive"))
      (node (ref "C9") (pin "2") (pinfunction "2_2") (pintype "passive"))
      (node (ref "IC5") (pin "3") (pinfunction "VIN_3") (pintype "input"))
      (node (ref "L4.7") (pin "P$2") (pinfunction "2_P$2") (pintype "passive"))
      (node (ref "R11") (pin "1") (pinfunction "1_1") (pintype "passive"))
      (node (ref "R5") (pin "2") (pinfunction "2_2") (pintype "passive"))
      (node (ref "X1") (pin "2") (pinfunction "5V_2") (pintype "power_in"))
      (node (ref "X1") (pin "4") (pinfunction "5V_4") (pintype "power_in"))
    )
    (net (code "41") (name "Net-(IC6-BST)") (class "Default")
      (node (ref "C8") (pin "1") (pinfunction "1_1") (pintype "passive"))
      (node (ref "IC6") (pin "6") (pinfunction "BST_6") (pintype "input"))
    )
    (net (code "42") (name "Net-(IC6-FB)") (class "Default")
      (node (ref "IC6") (pin "4") (pinfunction "FB_4") (pintype "input"))
      (node (ref "R10") (pin "2") (pinfunction "2_2") (pintype "passive"))
      (node (ref "R11") (pin "2") (pinfunction "2_2") (pintype "passive"))
    )
    (net (code "43") (name "Net-(IC6-SW)") (class "Default")
      (node (ref "C8") (pin "2") (pinfunction "2_2") (pintype "passive"))
      (node (ref "IC6") (pin "2") (pinfunction "SW_2") (pintype "passive"))
      (node (ref "L4.7") (pin "P$1") (pinfunction "1_P$1") (pintype "passive"))
    )
    (net (code "44") (name "Net-(JP2-Pad1)") (class "Default")
      (node (ref "JP2") (pin "1") (pinfunction "1_1") (pintype "passive"))
      (node (ref "R22") (pin "1") (pinfunction "1_1") (pintype "passive"))
    )
    (net (code "45") (name "Net-(JP3-Pad1)") (class "Default")
      (node (ref "JP3") (pin "1") (pinfunction "1_1") (pintype "passive"))
      (node (ref "R23") (pin "1") (pinfunction "1_1") (pintype "passive"))
    )
    (net (code "46") (name "Net-(LED1-PadC)") (class "Default")
      (node (ref "LED1") (pin "C") (pinfunction "C_C") (pintype "passive"))
      (node (ref "R24") (pin "2") (pinfunction "2_2") (pintype "passive"))
    )
    (net (code "47") (name "Net-(LED2-PadC)") (class "Default")
      (node (ref "LED2") (pin "C") (pinfunction "C_C") (pintype "passive"))
      (node (ref "R18") (pin "2") (pinfunction "2_2") (pintype "passive"))
    )
    (net (code "48") (name "Net-(LED3-PadC)") (class "Default")
      (node (ref "LED3") (pin "C") (pinfunction "C_C") (pintype "passive"))
      (node (ref "R21") (pin "2") (pinfunction "2_2") (pintype "passive"))
    )
    (net (code "49") (name "Net-(LED4-PadC)") (class "Default")
      (node (ref "LED4") (pin "C") (pinfunction "C_C") (pintype "passive"))
      (node (ref "R27") (pin "2") (pinfunction "2_2") (pintype "passive"))
    )
    (net (code "50") (name "Net-(Q1-D)") (class "Default")
      (node (ref "D2") (pin "A") (pinfunction "A_A") (pintype "passive"))
      (node (ref "K2") (pin "1") (pinfunction "1_1") (pintype "passive"))
      (node (ref "Q1") (pin "3") (pinfunction "D_3") (pintype "passive"))
      (node (ref "R24") (pin "1") (pinfunction "1_1") (pintype "passive"))
    )
    (net (code "51") (name "Net-(Q1-G)") (class "Default")
      (node (ref "Q1") (pin "1") (pinfunction "G_1") (pintype "passive"))
      (node (ref "R9") (pin "1") (pinfunction "1_1") (pintype "passive"))
    )
    (net (code "52") (name "Net-(Q2-D)") (class "Default")
      (node (ref "D1") (pin "A") (pinfunction "A_A") (pintype "passive"))
      (node (ref "K1") (pin "1") (pinfunction "1_1") (pintype "passive"))
      (node (ref "Q2") (pin "3") (pinfunction "D_3") (pintype "passive"))
      (node (ref "R18") (pin "1") (pinfunction "1_1") (pintype "passive"))
    )
    (net (code "53") (name "Net-(Q2-G)") (class "Default")
      (node (ref "Q2") (pin "1") (pinfunction "G_1") (pintype "passive"))
      (node (ref "R16") (pin "1") (pinfunction "1_1") (pintype "passive"))
    )
    (net (code "54") (name "Net-(Q3-D)") (class "Default")
      (node (ref "D3") (pin "A") (pinfunction "A_A") (pintype "passive"))
      (node (ref "K3") (pin "1") (pinfunction "1_1") (pintype "passive"))
      (node (ref "Q3") (pin "3") (pinfunction "D_3") (pintype "passive"))
      (node (ref "R21") (pin "1") (pinfunction "1_1") (pintype "passive"))
    )
    (net (code "55") (name "Net-(Q3-G)") (class "Default")
      (node (ref "Q3") (pin "1") (pinfunction "G_1") (pintype "passive"))
      (node (ref "R19") (pin "1") (pinfunction "1_1") (pintype "passive"))
    )
    (net (code "56") (name "Net-(Q4-D)") (class "Default")
      (node (ref "D4") (pin "A") (pinfunction "A_A") (pintype "passive"))
      (node (ref "K4") (pin "1") (pinfunction "1_1") (pintype "passive"))
      (node (ref "Q4") (pin "3") (pinfunction "D_3") (pintype "passive"))
      (node (ref "R27") (pin "1") (pinfunction "1_1") (pintype "passive"))
    )
    (net (code "57") (name "Net-(Q4-G)") (class "Default")
      (node (ref "Q4") (pin "1") (pinfunction "G_1") (pintype "passive"))
      (node (ref "R25") (pin "1") (pinfunction "1_1") (pintype "passive"))
    )
    (net (code "58") (name "Net-(X1-UART1_RX{slash}PG07)") (class "Default")
      (node (ref "R1") (pin "2") (pinfunction "2_2") (pintype "passive"))
      (node (ref "R3") (pin "2") (pinfunction "2_2") (pintype "passive"))
      (node (ref "X1") (pin "10") (pinfunction "UART1_RX/PG07_10") (pintype "bidirectional"))
    )
    (net (code "59") (name "Net-(X1-UART1_TX{slash}PG06)") (class "Default")
      (node (ref "R2") (pin "2") (pinfunction "2_2") (pintype "passive"))
      (node (ref "R4") (pin "2") (pinfunction "2_2") (pintype "passive"))
      (node (ref "X1") (pin "8") (pinfunction "UART1_TX/PG06_8") (pintype "bidirectional"))
    )
    (net (code "60") (name "Net-(X3A-KL)") (class "Default")
      (node (ref "K1") (pin "O") (pinfunction "O_O") (pintype "passive"))
      (node (ref "X3") (pin "1") (pinfunction "KL_1") (pintype "passive"))
    )
    (net (code "61") (name "Net-(X3B-KL)") (class "Default")
      (node (ref "K1") (pin "P") (pinfunction "P_P") (pintype "passive"))
      (node (ref "X3") (pin "2") (pinfunction "KL_2") (pintype "passive"))
    )
    (net (code "62") (name "Net-(X3C-KL)") (class "Default")
      (node (ref "K1") (pin "S") (pinfunction "S_S") (pintype "passive"))
      (node (ref "X3") (pin "3") (pinfunction "KL_3") (pintype "passive"))
    )
    (net (code "63") (name "Net-(X4A-KL)") (class "Default")
      (node (ref "K2") (pin "O") (pinfunction "O_O") (pintype "passive"))
      (node (ref "X4") (pin "1") (pinfunction "KL_1") (pintype "passive"))
    )
    (net (code "64") (name "Net-(X4B-KL)") (class "Default")
      (node (ref "K2") (pin "P") (pinfunction "P_P") (pintype "passive"))
      (node (ref "X4") (pin "2") (pinfunction "KL_2") (pintype "passive"))
    )
    (net (code "65") (name "Net-(X4C-KL)") (class "Default")
      (node (ref "K2") (pin "S") (pinfunction "S_S") (pintype "passive"))
      (node (ref "X4") (pin "3") (pinfunction "KL_3") (pintype "passive"))
    )
    (net (code "66") (name "Net-(X5A-KL)") (class "Default")
      (node (ref "K3") (pin "O") (pinfunction "O_O") (pintype "passive"))
      (node (ref "X5") (pin "1") (pinfunction "KL_1") (pintype "passive"))
    )
    (net (code "67") (name "Net-(X5B-KL)") (class "Default")
      (node (ref "K3") (pin "P") (pinfunction "P_P") (pintype "passive"))
      (node (ref "X5") (pin "2") (pinfunction "KL_2") (pintype "passive"))
    )
    (net (code "68") (name "Net-(X5C-KL)") (class "Default")
      (node (ref "K3") (pin "S") (pinfunction "S_S") (pintype "passive"))
      (node (ref "X5") (pin "3") (pinfunction "KL_3") (pintype "passive"))
    )
    (net (code "69") (name "Net-(X6A-KL)") (class "Default")
      (node (ref "K4") (pin "O") (pinfunction "O_O") (pintype "passive"))
      (node (ref "X6") (pin "1") (pinfunction "KL_1") (pintype "passive"))
    )
    (net (code "70") (name "Net-(X6B-KL)") (class "Default")
      (node (ref "K4") (pin "P") (pinfunction "P_P") (pintype "passive"))
      (node (ref "X6") (pin "2") (pinfunction "KL_2") (pintype "passive"))
    )
    (net (code "71") (name "Net-(X6C-KL)") (class "Default")
      (node (ref "K4") (pin "S") (pinfunction "S_S") (pintype "passive"))
      (node (ref "X6") (pin "3") (pinfunction "KL_3") (pintype "passive"))
    )
    (net (code "72") (name "VDD") (class "Default")
      (node (ref "1W-1") (pin "1") (pinfunction "K_1") (pintype "passive"))
      (node (ref "1W-2") (pin "1") (pinfunction "K_1") (pintype "passive"))
      (node (ref "C6") (pin "1") (pinfunction "1_1") (pintype "passive"))
      (node (ref "C7") (pin "1") (pinfunction "1_1") (pintype "passive"))
      (node (ref "D7") (pin "C") (pinfunction "C_C") (pintype "passive"))
      (node (ref "D8") (pin "2") (pinfunction "C2_2") (pintype "passive"))
      (node (ref "D9") (pin "2") (pinfunction "C2_2") (pintype "passive"))
      (node (ref "IC3") (pin "7") (pinfunction "AD1_7") (pintype "input"))
      (node (ref "IC5") (pin "2") (pinfunction "VOUT_2") (pintype "passive"))
      (node (ref "Q5") (pin "2") (pinfunction "S_2") (pintype "passive"))
      (node (ref "Q6") (pin "2") (pinfunction "S_2") (pintype "passive"))
      (node (ref "R31") (pin "2") (pinfunction "2_2") (pintype "passive"))
    )
    (net (code "73") (name "unconnected-(IC1-PC3(ADC3{slash}PCINT11)-Pad26)") (class "Default")
      (node (ref "IC1") (pin "26") (pinfunction "PC3(ADC3/PCINT11)_26") (pintype "bidirectional"))
    )
    (net (code "74") (name "unconnected-(IC1-PD3(INT1{slash}OC2B{slash}PCINT19)-Pad1)") (class "Default")
      (node (ref "IC1") (pin "1") (pinfunction "PD3(INT1/OC2B/PCINT19)_1") (pintype "bidirectional"))
    )
    (net (code "75") (name "unconnected-(IC1-PD4(T0{slash}XCK{slash}PCINT20)-Pad2)") (class "Default")
      (node (ref "IC1") (pin "2") (pinfunction "PD4(T0/XCK/PCINT20)_2") (pintype "bidirectional"))
    )
    (net (code "76") (name "unconnected-(X1-PA13{slash}SPI1_CS-Pad24)") (class "Default")
      (node (ref "X1") (pin "24") (pinfunction "PA13/SPI1_CS_24") (pintype "bidirectional"))
    )
    (net (code "77") (name "unconnected-(X1-PA14{slash}SPI1_CLK-Pad23)") (class "Default")
      (node (ref "X1") (pin "23") (pinfunction "PA14/SPI1_CLK_23") (pintype "bidirectional"))
    )
    (net (code "78") (name "unconnected-(X1-PA15{slash}SPI1_MOSI-Pad19)") (class "Default")
      (node (ref "X1") (pin "19") (pinfunction "PA15/SPI1_MOSI_19") (pintype "bidirectional"))
    )
    (net (code "79") (name "unconnected-(X1-PA16{slash}SPI1_MISO-Pad21)") (class "Default")
      (node (ref "X1") (pin "21") (pinfunction "PA16/SPI1_MISO_21") (pintype "bidirectional"))
    )
    (net (code "80") (name "unconnected-(X1-PA18{slash}TWI1_SCL-Pad18)") (class "Default")
      (node (ref "X1") (pin "18") (pinfunction "PA18/TWI1_SCL_18") (pintype "bidirectional"))
    )
    (net (code "81") (name "unconnected-(X1-PA19{slash}TWI1_SDA-Pad16)") (class "Default")
      (node (ref "X1") (pin "16") (pinfunction "PA19/TWI1_SDA_16") (pintype "bidirectional"))
    )
    (net (code "82") (name "unconnected-(X1-PWM1{slash}PA06-Pad7)") (class "Default")
      (node (ref "X1") (pin "7") (pinfunction "PWM1/PA06_7") (pintype "bidirectional"))
    )
    (net (code "83") (name "unconnected-(X1-SIM_CLK{slash}PA_EINT7{slash}PA07-Pad12)") (class "Default")
      (node (ref "X1") (pin "12") (pinfunction "SIM_CLK/PA_EINT7/PA07_12") (pintype "bidirectional"))
    )
    (net (code "84") (name "unconnected-(X1-SIM_DET{slash}PA_EINT10{slash}PA10-Pad26)") (class "Default")
      (node (ref "X1") (pin "26") (pinfunction "SIM_DET/PA_EINT10/PA10_26") (pintype "bidirectional"))
    )
    (net (code "85") (name "unconnected-(X1-UART2_CTS{slash}PA03-Pad15)") (class "Default")
      (node (ref "X1") (pin "15") (pinfunction "UART2_CTS/PA03_15") (pintype "bidirectional"))
    )
    (net (code "86") (name "unconnected-(X1-UART2_RTS{slash}PA02-Pad22)") (class "Default")
      (node (ref "X1") (pin "22") (pinfunction "UART2_RTS/PA02_22") (pintype "bidirectional"))
    )
    (net (code "87") (name "unconnected-(X1-UART2_RX{slash}PA01-Pad11)") (class "Default")
      (node (ref "X1") (pin "11") (pinfunction "UART2_RX/PA01_11") (pintype "bidirectional"))
    )
    (net (code "88") (name "unconnected-(X1-UART2_TX{slash}PA00-Pad13)") (class "Default")
      (node (ref "X1") (pin "13") (pinfunction "UART2_TX/PA00_13") (pintype "bidirectional"))
    )
  )
)
